# LED.net
KiCad netlist of a schematic drawn in Altium Designer
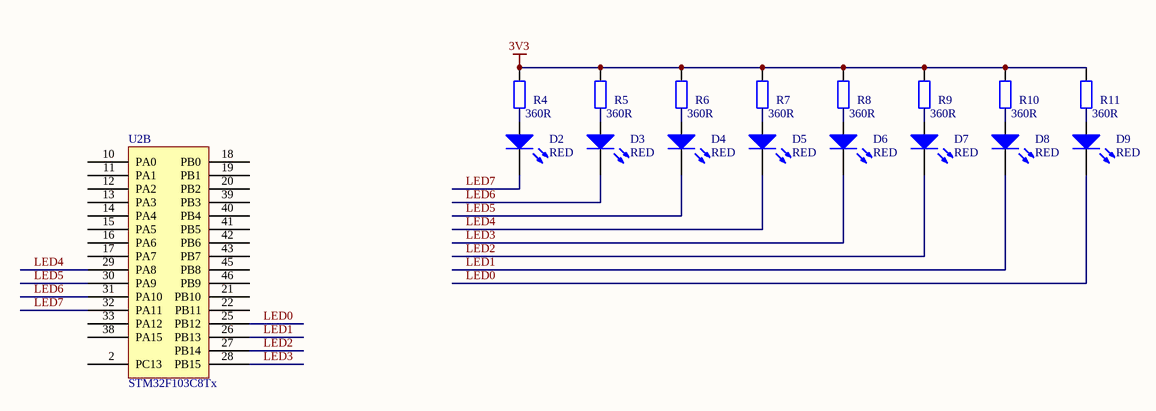
[diagram p0: LED.SchDoc]

(export (version "E")
  (design (tool "Eeschema 10.0.6"))
  (components
    (comp (ref "D2")
      (value "RED")
      (footprint "LED0603-RED")
      (description "Typical INFRARED GaAs LED")
      (fields (field (name "PUBLISHER") "Altium Limited"))
      (libsource (lib "Miscellaneous Devices") (part "LED0"))
    )
    (comp (ref "D3")
      (value "RED")
      (footprint "LED0603-RED")
      (description "Typical INFRARED GaAs LED")
      (fields (field (name "PUBLISHER") "Altium Limited"))
      (libsource (lib "Miscellaneous Devices") (part "LED0"))
    )
    (comp (ref "D4")
      (value "RED")
      (footprint "LED0603-RED")
      (description "Typical INFRARED GaAs LED")
      (fields (field (name "PUBLISHER") "Altium Limited"))
      (libsource (lib "Miscellaneous Devices") (part "LED0"))
    )
    (comp (ref "D5")
      (value "RED")
      (footprint "LED0603-RED")
      (description "Typical INFRARED GaAs LED")
      (fields (field (name "PUBLISHER") "Altium Limited"))
      (libsource (lib "Miscellaneous Devices") (part "LED0"))
    )
    (comp (ref "D6")
      (value "RED")
      (footprint "LED0603-RED")
      (description "Typical INFRARED GaAs LED")
      (fields (field (name "PUBLISHER") "Altium Limited"))
      (libsource (lib "Miscellaneous Devices") (part "LED0"))
    )
    (comp (ref "D7")
      (value "RED")
      (footprint "LED0603-RED")
      (description "Typical INFRARED GaAs LED")
      (fields (field (name "PUBLISHER") "Altium Limited"))
      (libsource (lib "Miscellaneous Devices") (part "LED0"))
    )
    (comp (ref "D8")
      (value "RED")
      (footprint "LED0603-RED")
      (description "Typical INFRARED GaAs LED")
      (fields (field (name "PUBLISHER") "Altium Limited"))
      (libsource (lib "Miscellaneous Devices") (part "LED0"))
    )
    (comp (ref "D9")
      (value "RED")
      (footprint "LED0603-RED")
      (description "Typical INFRARED GaAs LED")
      (fields (field (name "PUBLISHER") "Altium Limited"))
      (libsource (lib "Miscellaneous Devices") (part "LED0"))
    )
    (comp (ref "R4")
      (value "360R")
      (footprint "R0603")
      (description "Resistor")
      (fields (field (name "PUBLISHER") "Altium Limited"))
      (libsource (lib "Miscellaneous Devices") (part "Res2"))
    )
    (comp (ref "R5")
      (value "360R")
      (footprint "R0603")
      (description "Resistor")
      (fields (field (name "PUBLISHER") "Altium Limited"))
      (libsource (lib "Miscellaneous Devices") (part "Res2"))
    )
    (comp (ref "R6")
      (value "360R")
      (footprint "R0603")
      (description "Resistor")
      (fields (field (name "PUBLISHER") "Altium Limited"))
      (libsource (lib "Miscellaneous Devices") (part "Res2"))
    )
    (comp (ref "R7")
      (value "360R")
      (footprint "R0603")
      (description "Resistor")
      (fields (field (name "PUBLISHER") "Altium Limited"))
      (libsource (lib "Miscellaneous Devices") (part "Res2"))
    )
    (comp (ref "R8")
      (value "360R")
      (footprint "R0603")
      (description "Resistor")
      (fields (field (name "PUBLISHER") "Altium Limited"))
      (libsource (lib "Miscellaneous Devices") (part "Res2"))
    )
    (comp (ref "R9")
      (value "360R")
      (footprint "R0603")
      (description "Resistor")
      (fields (field (name "PUBLISHER") "Altium Limited"))
      (libsource (lib "Miscellaneous Devices") (part "Res2"))
    )
    (comp (ref "R10")
      (value "360R")
      (footprint "R0603")
      (description "Resistor")
      (fields (field (name "PUBLISHER") "Altium Limited"))
      (libsource (lib "Miscellaneous Devices") (part "Res2"))
    )
    (comp (ref "R11")
      (value "360R")
      (footprint "R0603")
      (description "Resistor")
      (fields (field (name "PUBLISHER") "Altium Limited"))
      (libsource (lib "Miscellaneous Devices") (part "Res2"))
    )
    (comp (ref "U2")
      (value "STM32F103C8Tx")
      (footprint "PQFP48")
      (libsource (lib "yinhaonanLib") (part "STM32F103C8Tx"))
    )
  )
  (nets
    (net (code "1") (name "/LED0") (class "Default")
      (node (ref "D9") (pin "2") (pinfunction "K_2") (pintype "passive"))
      (node (ref "U2") (pin "25") (pinfunction "PB12_25") (pintype "passive"))
    )
    (net (code "2") (name "/LED1") (class "Default")
      (node (ref "D8") (pin "2") (pinfunction "K_2") (pintype "passive"))
      (node (ref "U2") (pin "26") (pinfunction "PB13_26") (pintype "passive"))
    )
    (net (code "3") (name "/LED2") (class "Default")
      (node (ref "D7") (pin "2") (pinfunction "K_2") (pintype "passive"))
      (node (ref "U2") (pin "27") (pinfunction "PB14_27") (pintype "passive"))
    )
    (net (code "4") (name "/LED3") (class "Default")
      (node (ref "D6") (pin "2") (pinfunction "K_2") (pintype "passive"))
      (node (ref "U2") (pin "28") (pinfunction "PB15_28") (pintype "passive"))
    )
    (net (code "5") (name "/LED4") (class "Default")
      (node (ref "D5") (pin "2") (pinfunction "K_2") (pintype "passive"))
      (node (ref "U2") (pin "29") (pinfunction "PA8_29") (pintype "passive"))
    )
    (net (code "6") (name "/LED5") (class "Default")
      (node (ref "D4") (pin "2") (pinfunction "K_2") (pintype "passive"))
      (node (ref "U2") (pin "30") (pinfunction "PA9_30") (pintype "passive"))
    )
    (net (code "7") (name "/LED6") (class "Default")
      (node (ref "D3") (pin "2") (pinfunction "K_2") (pintype "passive"))
      (node (ref "U2") (pin "31") (pinfunction "PA10_31") (pintype "passive"))
    )
    (net (code "8") (name "/LED7") (class "Default")
      (node (ref "D2") (pin "2") (pinfunction "K_2") (pintype "passive"))
      (node (ref "U2") (pin "32") (pinfunction "PA11_32") (pintype "passive"))
    )
    (net (code "9") (name "3V3") (class "Default")
      (node (ref "R10") (pin "1") (pinfunction "1_1") (pintype "passive"))
      (node (ref "R11") (pin "1") (pinfunction "1_1") (pintype "passive"))
      (node (ref "R4") (pin "1") (pinfunction "1_1") (pintype "passive"))
      (node (ref "R5") (pin "1") (pinfunction "1_1") (pintype "passive"))
      (node (ref "R6") (pin "1") (pinfunction "1_1") (pintype "passive"))
      (node (ref "R7") (pin "1") (pinfunction "1_1") (pintype "passive"))
      (node (ref "R8") (pin "1") (pinfunction "1_1") (pintype "passive"))
      (node (ref "R9") (pin "1") (pinfunction "1_1") (pintype "passive"))
    )
    (net (code "10") (name "Net-(D2-A)") (class "Default")
      (node (ref "D2") (pin "1") (pinfunction "A_1") (pintype "passive"))
      (node (ref "R4") (pin "2") (pinfunction "2_2") (pintype "passive"))
    )
    (net (code "11") (name "Net-(D3-A)") (class "Default")
      (node (ref "D3") (pin "1") (pinfunction "A_1") (pintype "passive"))
      (node (ref "R5") (pin "2") (pinfunction "2_2") (pintype "passive"))
    )
    (net (code "12") (name "Net-(D4-A)") (class "Default")
      (node (ref "D4") (pin "1") (pinfunction "A_1") (pintype "passive"))
      (node (ref "R6") (pin "2") (pinfunction "2_2") (pintype "passive"))
    )
    (net (code "13") (name "Net-(D5-A)") (class "Default")
      (node (ref "D5") (pin "1") (pinfunction "A_1") (pintype "passive"))
      (node (ref "R7") (pin "2") (pinfunction "2_2") (pintype "passive"))
    )
    (net (code "14") (name "Net-(D6-A)") (class "Default")
      (node (ref "D6") (pin "1") (pinfunction "A_1") (pintype "passive"))
      (node (ref "R8") (pin "2") (pinfunction "2_2") (pintype "passive"))
    )
    (net (code "15") (name "Net-(D7-A)") (class "Default")
      (node (ref "D7") (pin "1") (pinfunction "A_1") (pintype "passive"))
      (node (ref "R9") (pin "2") (pinfunction "2_2") (pintype "passive"))
    )
    (net (code "16") (name "Net-(D8-A)") (class "Default")
      (node (ref "D8") (pin "1") (pinfunction "A_1") (pintype "passive"))
      (node (ref "R10") (pin "2") (pinfunction "2_2") (pintype "passive"))
    )
    (net (code "17") (name "Net-(D9-A)") (class "Default")
      (node (ref "D9") (pin "1") (pinfunction "A_1") (pintype "passive"))
      (node (ref "R11") (pin "2") (pinfunction "2_2") (pintype "passive"))
    )
    (net (code "18") (name "unconnected-(U2B-PA0-Pad10)") (class "Default")
      (node (ref "U2") (pin "10") (pinfunction "PA0_10") (pintype "passive"))
    )
    (net (code "19") (name "unconnected-(U2B-PA1-Pad11)") (class "Default")
      (node (ref "U2") (pin "11") (pinfunction "PA1_11") (pintype "passive"))
    )
    (net (code "20") (name "unconnected-(U2B-PA2-Pad12)") (class "Default")
      (node (ref "U2") (pin "12") (pinfunction "PA2_12") (pintype "passive"))
    )
    (net (code "21") (name "unconnected-(U2B-PA3-Pad13)") (class "Default")
      (node (ref "U2") (pin "13") (pinfunction "PA3_13") (pintype "passive"))
    )
    (net (code "22") (name "unconnected-(U2B-PA4-Pad14)") (class "Default")
      (node (ref "U2") (pin "14") (pinfunction "PA4_14") (pintype "passive"))
    )
    (net (code "23") (name "unconnected-(U2B-PA5-Pad15)") (class "Default")
      (node (ref "U2") (pin "15") (pinfunction "PA5_15") (pintype "passive"))
    )
    (net (code "24") (name "unconnected-(U2B-PA6-Pad16)") (class "Default")
      (node (ref "U2") (pin "16") (pinfunction "PA6_16") (pintype "passive"))
    )
    (net (code "25") (name "unconnected-(U2B-PA7-Pad17)") (class "Default")
      (node (ref "U2") (pin "17") (pinfunction "PA7_17") (pintype "passive"))
    )
    (net (code "26") (name "unconnected-(U2B-PA12-Pad33)") (class "Default")
      (node (ref "U2") (pin "33") (pinfunction "PA12_33") (pintype "passive"))
    )
    (net (code "27") (name "unconnected-(U2B-PA15-Pad38)") (class "Default")
      (node (ref "U2") (pin "38") (pinfunction "PA15_38") (pintype "passive"))
    )
    (net (code "28") (name "unconnected-(U2B-PB0-Pad18)") (class "Default")
      (node (ref "U2") (pin "18") (pinfunction "PB0_18") (pintype "passive"))
    )
    (net (code "29") (name "unconnected-(U2B-PB1-Pad19)") (class "Default")
      (node (ref "U2") (pin "19") (pinfunction "PB1_19") (pintype "passive"))
    )
    (net (code "30") (name "unconnected-(U2B-PB2-Pad20)") (class "Default")
      (node (ref "U2") (pin "20") (pinfunction "PB2_20") (pintype "passive"))
    )
    (net (code "31") (name "unconnected-(U2B-PB3-Pad39)") (class "Default")
      (node (ref "U2") (pin "39") (pinfunction "PB3_39") (pintype "passive"))
    )
    (net (code "32") (name "unconnected-(U2B-PB4-Pad40)") (class "Default")
      (node (ref "U2") (pin "40") (pinfunction "PB4_40") (pintype "passive"))
    )
    (net (code "33") (name "unconnected-(U2B-PB5-Pad41)") (class "Default")
      (node (ref "U2") (pin "41") (pinfunction "PB5_41") (pintype "passive"))
    )
    (net (code "34") (name "unconnected-(U2B-PB6-Pad42)") (class "Default")
      (node (ref "U2") (pin "42") (pinfunction "PB6_42") (pintype "passive"))
    )
    (net (code "35") (name "unconnected-(U2B-PB7-Pad43)") (class "Default")
      (node (ref "U2") (pin "43") (pinfunction "PB7_43") (pintype "passive"))
    )
    (net (code "36") (name "unconnected-(U2B-PB8-Pad45)") (class "Default")
      (node (ref "U2") (pin "45") (pinfunction "PB8_45") (pintype "passive"))
    )
    (net (code "37") (name "unconnected-(U2B-PB9-Pad46)") (class "Default")
      (node (ref "U2") (pin "46") (pinfunction "PB9_46") (pintype "passive"))
    )
    (net (code "38") (name "unconnected-(U2B-PB10-Pad21)") (class "Default")
      (node (ref "U2") (pin "21") (pinfunction "PB10_21") (pintype "passive"))
    )
    (net (code "39") (name "unconnected-(U2B-PB11-Pad22)") (class "Default")
      (node (ref "U2") (pin "22") (pinfunction "PB11_22") (pintype "passive"))
    )
    (net (code "40") (name "unconnected-(U2B-PC13-Pad2)") (class "Default")
      (node (ref "U2") (pin "2") (pinfunction "PC13_2") (pintype "passive"))
    )
  )
)
